# Guitar_Hero_Controller_PS2_to_PC_PCB.net
KiCad netlist of a schematic drawn in EAGLE
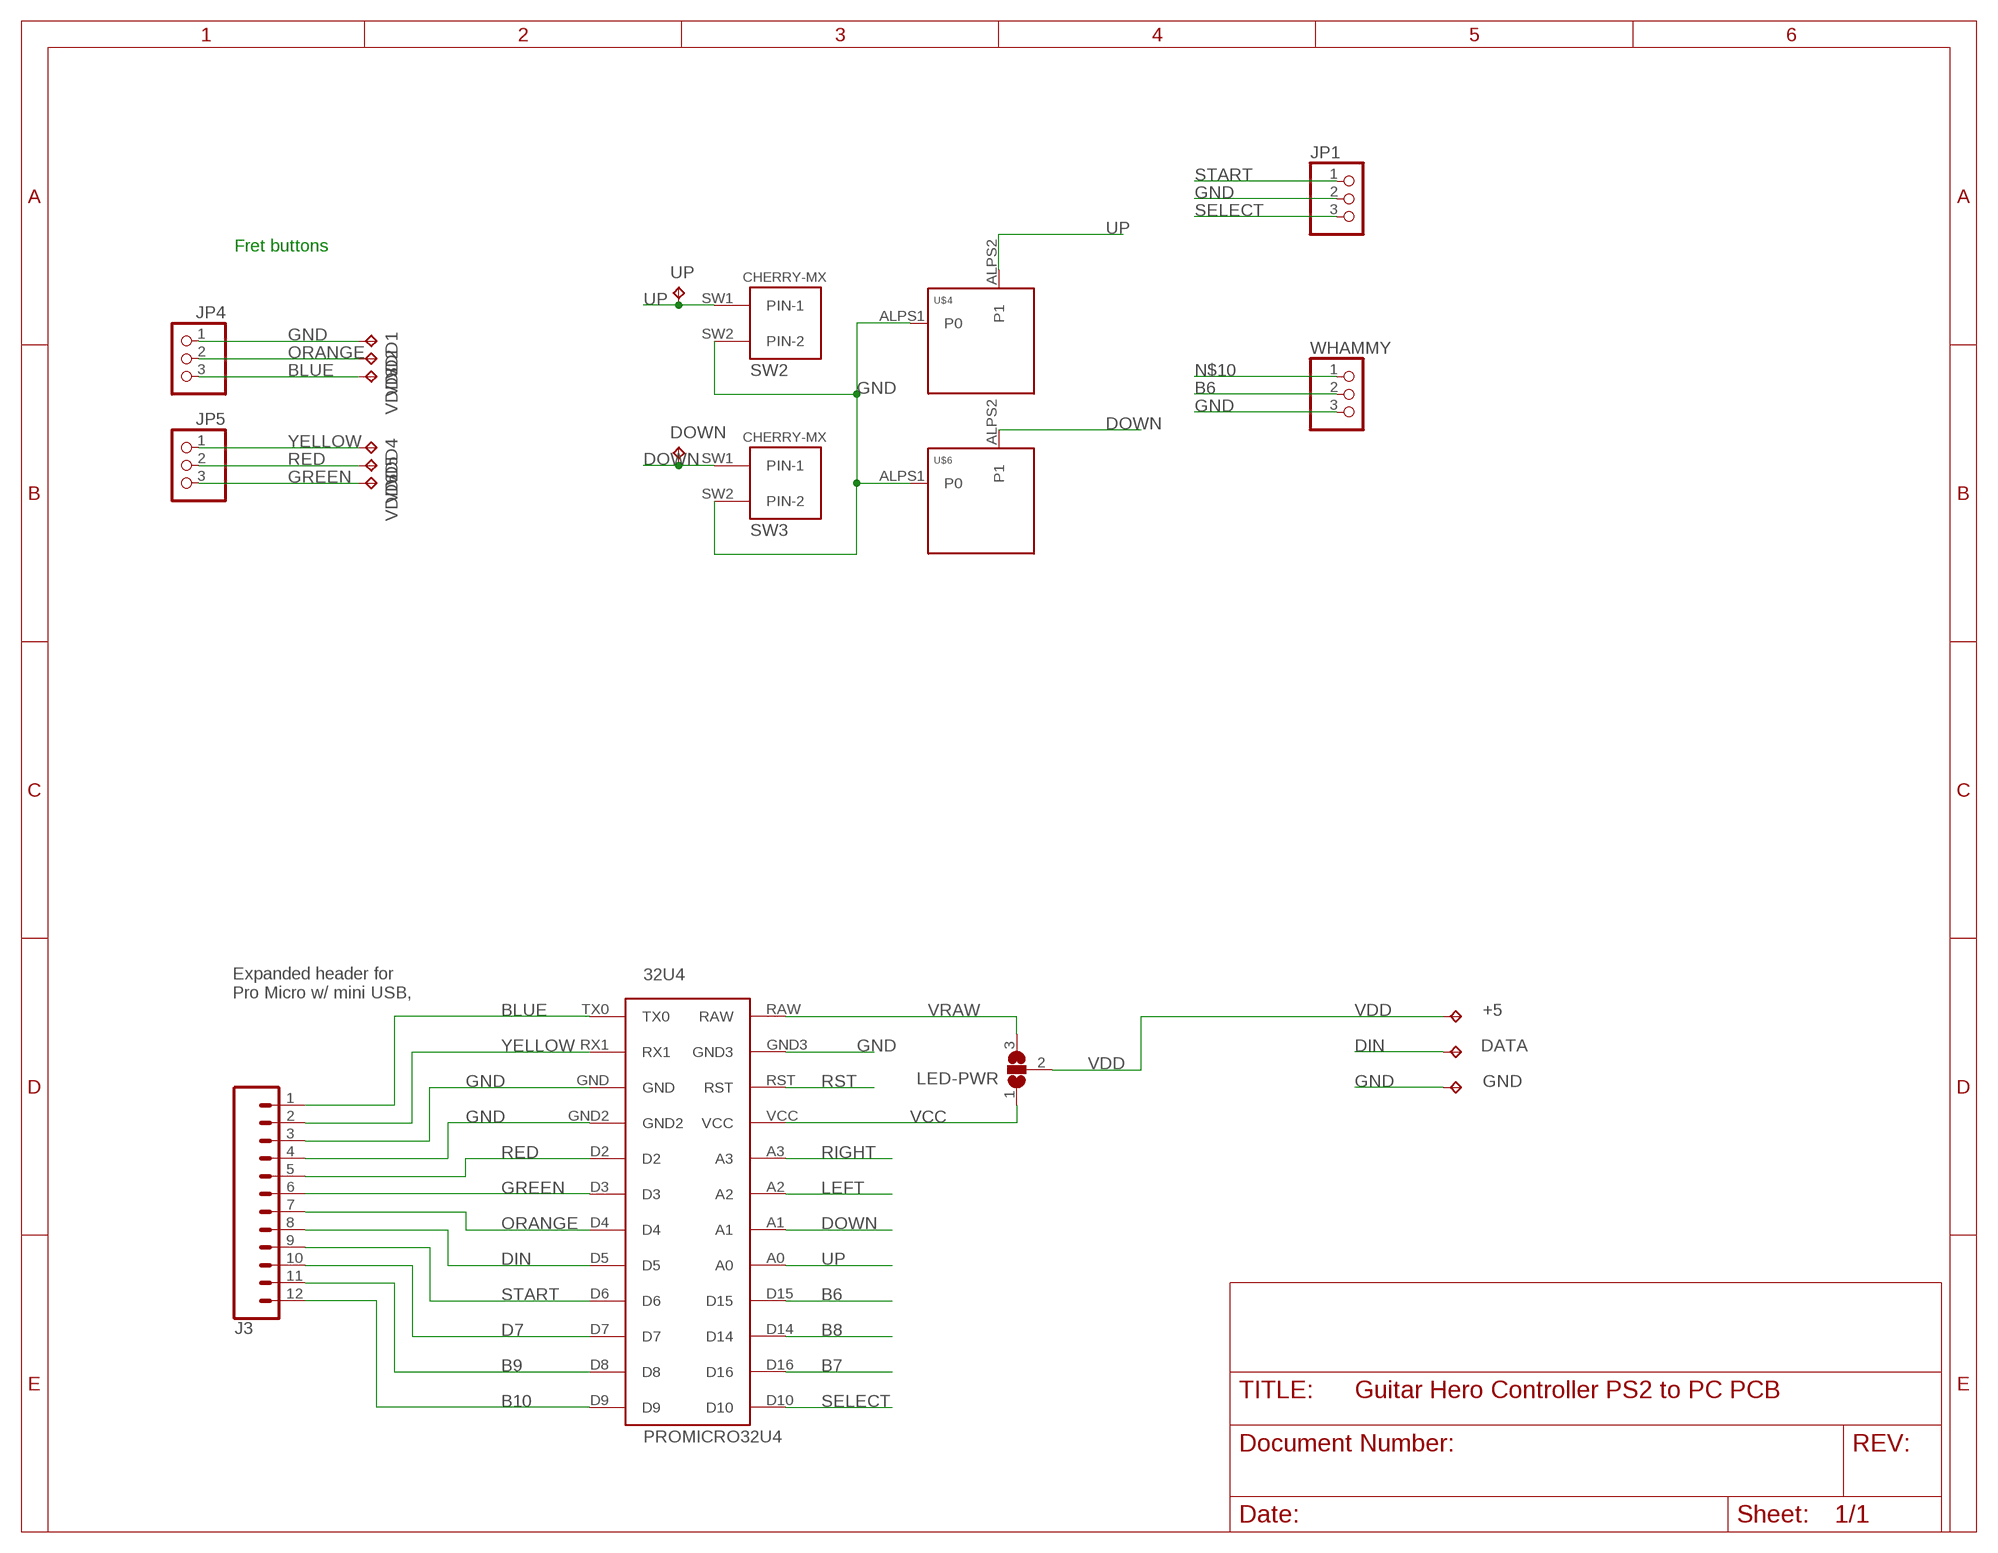
[diagram p0: schematic, sheet 1]

(export (version "E")
  (design (tool "Eeschema 10.0.6"))
  (components
    (comp (ref "+5")
      (value "TPTP20SQ")
      (footprint "eagle-import:TP20SQ")
      (libsource (lib "eagle-import") (part "testpad_385_TPTP20SQ"))
    )
    (comp (ref "32U4")
      (value "PROMICRO32U4")
      (footprint "eagle-import:PROMICRO32U4")
      (libsource (lib "eagle-import") (part "PROMICRO32U4"))
    )
    (comp (ref "DATA")
      (value "TPTP20SQ")
      (footprint "eagle-import:TP20SQ")
      (libsource (lib "eagle-import") (part "testpad_385_TPTP20SQ"))
    )
    (comp (ref "DOWN")
      (value "TPTP20R")
      (footprint "eagle-import:TP20R")
      (libsource (lib "eagle-import") (part "TPTP20R"))
    )
    (comp (ref "GND")
      (value "TPTP20SQ")
      (footprint "eagle-import:TP20SQ")
      (libsource (lib "eagle-import") (part "testpad_385_TPTP20SQ"))
    )
    (comp (ref "J3")
      (value "CONN_12NO_SILK")
      (footprint "eagle-import:1X12_NO_SILK")
      (libsource (lib "eagle-import") (part "CONN_12NO_SILK"))
    )
    (comp (ref "JP1")
      (value "PINHD-1X3CB")
      (footprint "eagle-import:1X03-CLEANBIG")
      (libsource (lib "eagle-import") (part "PINHD-1X3CB"))
    )
    (comp (ref "JP4")
      (value "PINHD-1X3CB")
      (footprint "eagle-import:1X03-CLEANBIG")
      (libsource (lib "eagle-import") (part "PINHD-1X3CB"))
    )
    (comp (ref "JP5")
      (value "PINHD-1X3CB")
      (footprint "eagle-import:1X03-CLEANBIG")
      (libsource (lib "eagle-import") (part "PINHD-1X3CB"))
    )
    (comp (ref "LED-PWR")
      (value "SJ2W")
      (footprint "eagle-import:SJ_2")
      (libsource (lib "eagle-import") (part "SJ2W"))
    )
    (comp (ref "SW2")
      (value "CHERRY-MX")
      (footprint "eagle-import:CHERRY-MX")
      (libsource (lib "eagle-import") (part "CHERRY-MX"))
    )
    (comp (ref "SW3")
      (value "CHERRY-MX")
      (footprint "eagle-import:CHERRY-MX")
      (libsource (lib "eagle-import") (part "CHERRY-MX"))
    )
    (comp (ref "U$4")
      (value "KEYSWITCH-PLAIN-ALPS-1U")
      (footprint "eagle-import:ALPS-1U")
      (libsource (lib "eagle-import") (part "KEYSWITCH-PLAIN-ALPS-1U"))
    )
    (comp (ref "U$6")
      (value "KEYSWITCH-PLAIN-ALPS-1U")
      (footprint "eagle-import:ALPS-1U")
      (libsource (lib "eagle-import") (part "KEYSWITCH-PLAIN-ALPS-1U"))
    )
    (comp (ref "UP")
      (value "TPTP20R")
      (footprint "eagle-import:TP20R")
      (libsource (lib "eagle-import") (part "TPTP20R"))
    )
    (comp (ref "VDD1")
      (value "TPTP20SQ")
      (footprint "eagle-import:TP20SQ")
      (libsource (lib "eagle-import") (part "testpad_385_TPTP20SQ"))
    )
    (comp (ref "VDD2")
      (value "TPTP20SQ")
      (footprint "eagle-import:TP20SQ")
      (libsource (lib "eagle-import") (part "testpad_385_TPTP20SQ"))
    )
    (comp (ref "VDD3")
      (value "TPTP20SQ")
      (footprint "eagle-import:TP20SQ")
      (libsource (lib "eagle-import") (part "testpad_385_TPTP20SQ"))
    )
    (comp (ref "VDD4")
      (value "TPTP20SQ")
      (footprint "eagle-import:TP20SQ")
      (libsource (lib "eagle-import") (part "testpad_385_TPTP20SQ"))
    )
    (comp (ref "VDD5")
      (value "TPTP20SQ")
      (footprint "eagle-import:TP20SQ")
      (libsource (lib "eagle-import") (part "testpad_385_TPTP20SQ"))
    )
    (comp (ref "VDD6")
      (value "TPTP20SQ")
      (footprint "eagle-import:TP20SQ")
      (libsource (lib "eagle-import") (part "testpad_385_TPTP20SQ"))
    )
    (comp (ref "WHAMMY")
      (value "PINHD-1X3CB")
      (footprint "eagle-import:1X03-CLEANBIG")
      (libsource (lib "eagle-import") (part "PINHD-1X3CB"))
    )
  )
  (nets
    (net (code "1") (name "/B6") (class "Default")
      (node (ref "32U4") (pin "D15") (pinfunction "D15_D15") (pintype "bidirectional"))
      (node (ref "WHAMMY") (pin "2") (pinfunction "2_2") (pintype "passive"))
    )
    (net (code "2") (name "/B7") (class "Default")
      (node (ref "32U4") (pin "D16") (pinfunction "D16_D16") (pintype "bidirectional"))
    )
    (net (code "3") (name "/B8") (class "Default")
      (node (ref "32U4") (pin "D14") (pinfunction "D14_D14") (pintype "bidirectional"))
    )
    (net (code "4") (name "/B9") (class "Default")
      (node (ref "32U4") (pin "D8") (pinfunction "D8_D8") (pintype "bidirectional"))
      (node (ref "J3") (pin "11") (pinfunction "11_11") (pintype "passive"))
    )
    (net (code "5") (name "/B10") (class "Default")
      (node (ref "32U4") (pin "D9") (pinfunction "D9_D9") (pintype "bidirectional"))
      (node (ref "J3") (pin "12") (pinfunction "12_12") (pintype "passive"))
    )
    (net (code "6") (name "/BLUE") (class "Default")
      (node (ref "32U4") (pin "TX0") (pinfunction "TX0_TX0") (pintype "bidirectional"))
      (node (ref "J3") (pin "1") (pinfunction "1_1") (pintype "passive"))
      (node (ref "JP4") (pin "3") (pinfunction "3_3") (pintype "passive"))
      (node (ref "VDD3") (pin "TP") (pinfunction "TP_TP") (pintype "input"))
    )
    (net (code "7") (name "/D7") (class "Default")
      (node (ref "32U4") (pin "D7") (pinfunction "D7_D7") (pintype "bidirectional"))
      (node (ref "J3") (pin "10") (pinfunction "10_10") (pintype "passive"))
    )
    (net (code "8") (name "/DIN") (class "Default")
      (node (ref "32U4") (pin "D5") (pinfunction "D5_D5") (pintype "bidirectional"))
      (node (ref "DATA") (pin "TP") (pinfunction "TP_TP") (pintype "input"))
      (node (ref "J3") (pin "8") (pinfunction "8_8") (pintype "passive"))
    )
    (net (code "9") (name "/DOWN") (class "Default")
      (node (ref "32U4") (pin "A1") (pinfunction "A1_A1") (pintype "bidirectional"))
      (node (ref "DOWN") (pin "TP") (pinfunction "TP_TP") (pintype "input"))
      (node (ref "SW3") (pin "SW1") (pinfunction "PIN-1_SW1") (pintype "bidirectional"))
      (node (ref "U$6") (pin "ALPS2") (pinfunction "P1_ALPS2") (pintype "bidirectional"))
    )
    (net (code "10") (name "/GND") (class "Default")
      (node (ref "32U4") (pin "GND") (pinfunction "GND_GND") (pintype "bidirectional"))
      (node (ref "32U4") (pin "GND2") (pinfunction "GND2_GND2") (pintype "bidirectional"))
      (node (ref "32U4") (pin "GND3") (pinfunction "GND3_GND3") (pintype "bidirectional"))
      (node (ref "GND") (pin "TP") (pinfunction "TP_TP") (pintype "input"))
      (node (ref "J3") (pin "3") (pinfunction "3_3") (pintype "passive"))
      (node (ref "J3") (pin "4") (pinfunction "4_4") (pintype "passive"))
      (node (ref "JP1") (pin "2") (pinfunction "2_2") (pintype "passive"))
      (node (ref "JP4") (pin "1") (pinfunction "1_1") (pintype "passive"))
      (node (ref "SW2") (pin "SW2") (pinfunction "PIN-2_SW2") (pintype "bidirectional"))
      (node (ref "SW3") (pin "SW2") (pinfunction "PIN-2_SW2") (pintype "bidirectional"))
      (node (ref "U$4") (pin "ALPS1") (pinfunction "P0_ALPS1") (pintype "bidirectional"))
      (node (ref "U$6") (pin "ALPS1") (pinfunction "P0_ALPS1") (pintype "bidirectional"))
      (node (ref "VDD1") (pin "TP") (pinfunction "TP_TP") (pintype "input"))
      (node (ref "WHAMMY") (pin "3") (pinfunction "3_3") (pintype "passive"))
    )
    (net (code "11") (name "/GREEN") (class "Default")
      (node (ref "32U4") (pin "D3") (pinfunction "D3_D3") (pintype "bidirectional"))
      (node (ref "J3") (pin "6") (pinfunction "6_6") (pintype "passive"))
      (node (ref "JP5") (pin "3") (pinfunction "3_3") (pintype "passive"))
      (node (ref "VDD6") (pin "TP") (pinfunction "TP_TP") (pintype "input"))
    )
    (net (code "12") (name "/LEFT") (class "Default")
      (node (ref "32U4") (pin "A2") (pinfunction "A2_A2") (pintype "bidirectional"))
    )
    (net (code "13") (name "/N$10") (class "Default")
      (node (ref "WHAMMY") (pin "1") (pinfunction "1_1") (pintype "passive"))
    )
    (net (code "14") (name "/ORANGE") (class "Default")
      (node (ref "32U4") (pin "D4") (pinfunction "D4_D4") (pintype "bidirectional"))
      (node (ref "J3") (pin "7") (pinfunction "7_7") (pintype "passive"))
      (node (ref "JP4") (pin "2") (pinfunction "2_2") (pintype "passive"))
      (node (ref "VDD2") (pin "TP") (pinfunction "TP_TP") (pintype "input"))
    )
    (net (code "15") (name "/RED") (class "Default")
      (node (ref "32U4") (pin "D2") (pinfunction "D2_D2") (pintype "bidirectional"))
      (node (ref "J3") (pin "5") (pinfunction "5_5") (pintype "passive"))
      (node (ref "JP5") (pin "2") (pinfunction "2_2") (pintype "passive"))
      (node (ref "VDD5") (pin "TP") (pinfunction "TP_TP") (pintype "input"))
    )
    (net (code "16") (name "/RIGHT") (class "Default")
      (node (ref "32U4") (pin "A3") (pinfunction "A3_A3") (pintype "bidirectional"))
    )
    (net (code "17") (name "/RST") (class "Default")
      (node (ref "32U4") (pin "RST") (pinfunction "RST_RST") (pintype "bidirectional"))
    )
    (net (code "18") (name "/SELECT") (class "Default")
      (node (ref "32U4") (pin "D10") (pinfunction "D10_D10") (pintype "bidirectional"))
      (node (ref "JP1") (pin "3") (pinfunction "3_3") (pintype "passive"))
    )
    (net (code "19") (name "/START") (class "Default")
      (node (ref "32U4") (pin "D6") (pinfunction "D6_D6") (pintype "bidirectional"))
      (node (ref "J3") (pin "9") (pinfunction "9_9") (pintype "passive"))
      (node (ref "JP1") (pin "1") (pinfunction "1_1") (pintype "passive"))
    )
    (net (code "20") (name "/UP") (class "Default")
      (node (ref "32U4") (pin "A0") (pinfunction "A0_A0") (pintype "bidirectional"))
      (node (ref "SW2") (pin "SW1") (pinfunction "PIN-1_SW1") (pintype "bidirectional"))
      (node (ref "U$4") (pin "ALPS2") (pinfunction "P1_ALPS2") (pintype "bidirectional"))
      (node (ref "UP") (pin "TP") (pinfunction "TP_TP") (pintype "input"))
    )
    (net (code "21") (name "/VCC") (class "Default")
      (node (ref "32U4") (pin "VCC") (pinfunction "VCC_VCC") (pintype "bidirectional"))
      (node (ref "LED-PWR") (pin "1") (pinfunction "1_1") (pintype "passive"))
    )
    (net (code "22") (name "/VDD") (class "Default")
      (node (ref "+5") (pin "TP") (pinfunction "TP_TP") (pintype "input"))
      (node (ref "LED-PWR") (pin "2") (pinfunction "2_2") (pintype "passive"))
    )
    (net (code "23") (name "/VRAW") (class "Default")
      (node (ref "32U4") (pin "RAW") (pinfunction "RAW_RAW") (pintype "bidirectional"))
      (node (ref "LED-PWR") (pin "3") (pinfunction "3_3") (pintype "passive"))
    )
    (net (code "24") (name "/YELLOW") (class "Default")
      (node (ref "32U4") (pin "RX1") (pinfunction "RX1_RX1") (pintype "bidirectional"))
      (node (ref "J3") (pin "2") (pinfunction "2_2") (pintype "passive"))
      (node (ref "JP5") (pin "1") (pinfunction "1_1") (pintype "passive"))
      (node (ref "VDD4") (pin "TP") (pinfunction "TP_TP") (pintype "input"))
    )
  )
)
